# Balancing_Robot_1_2_FTDI.net
KiCad netlist of a schematic drawn in Altium Designer
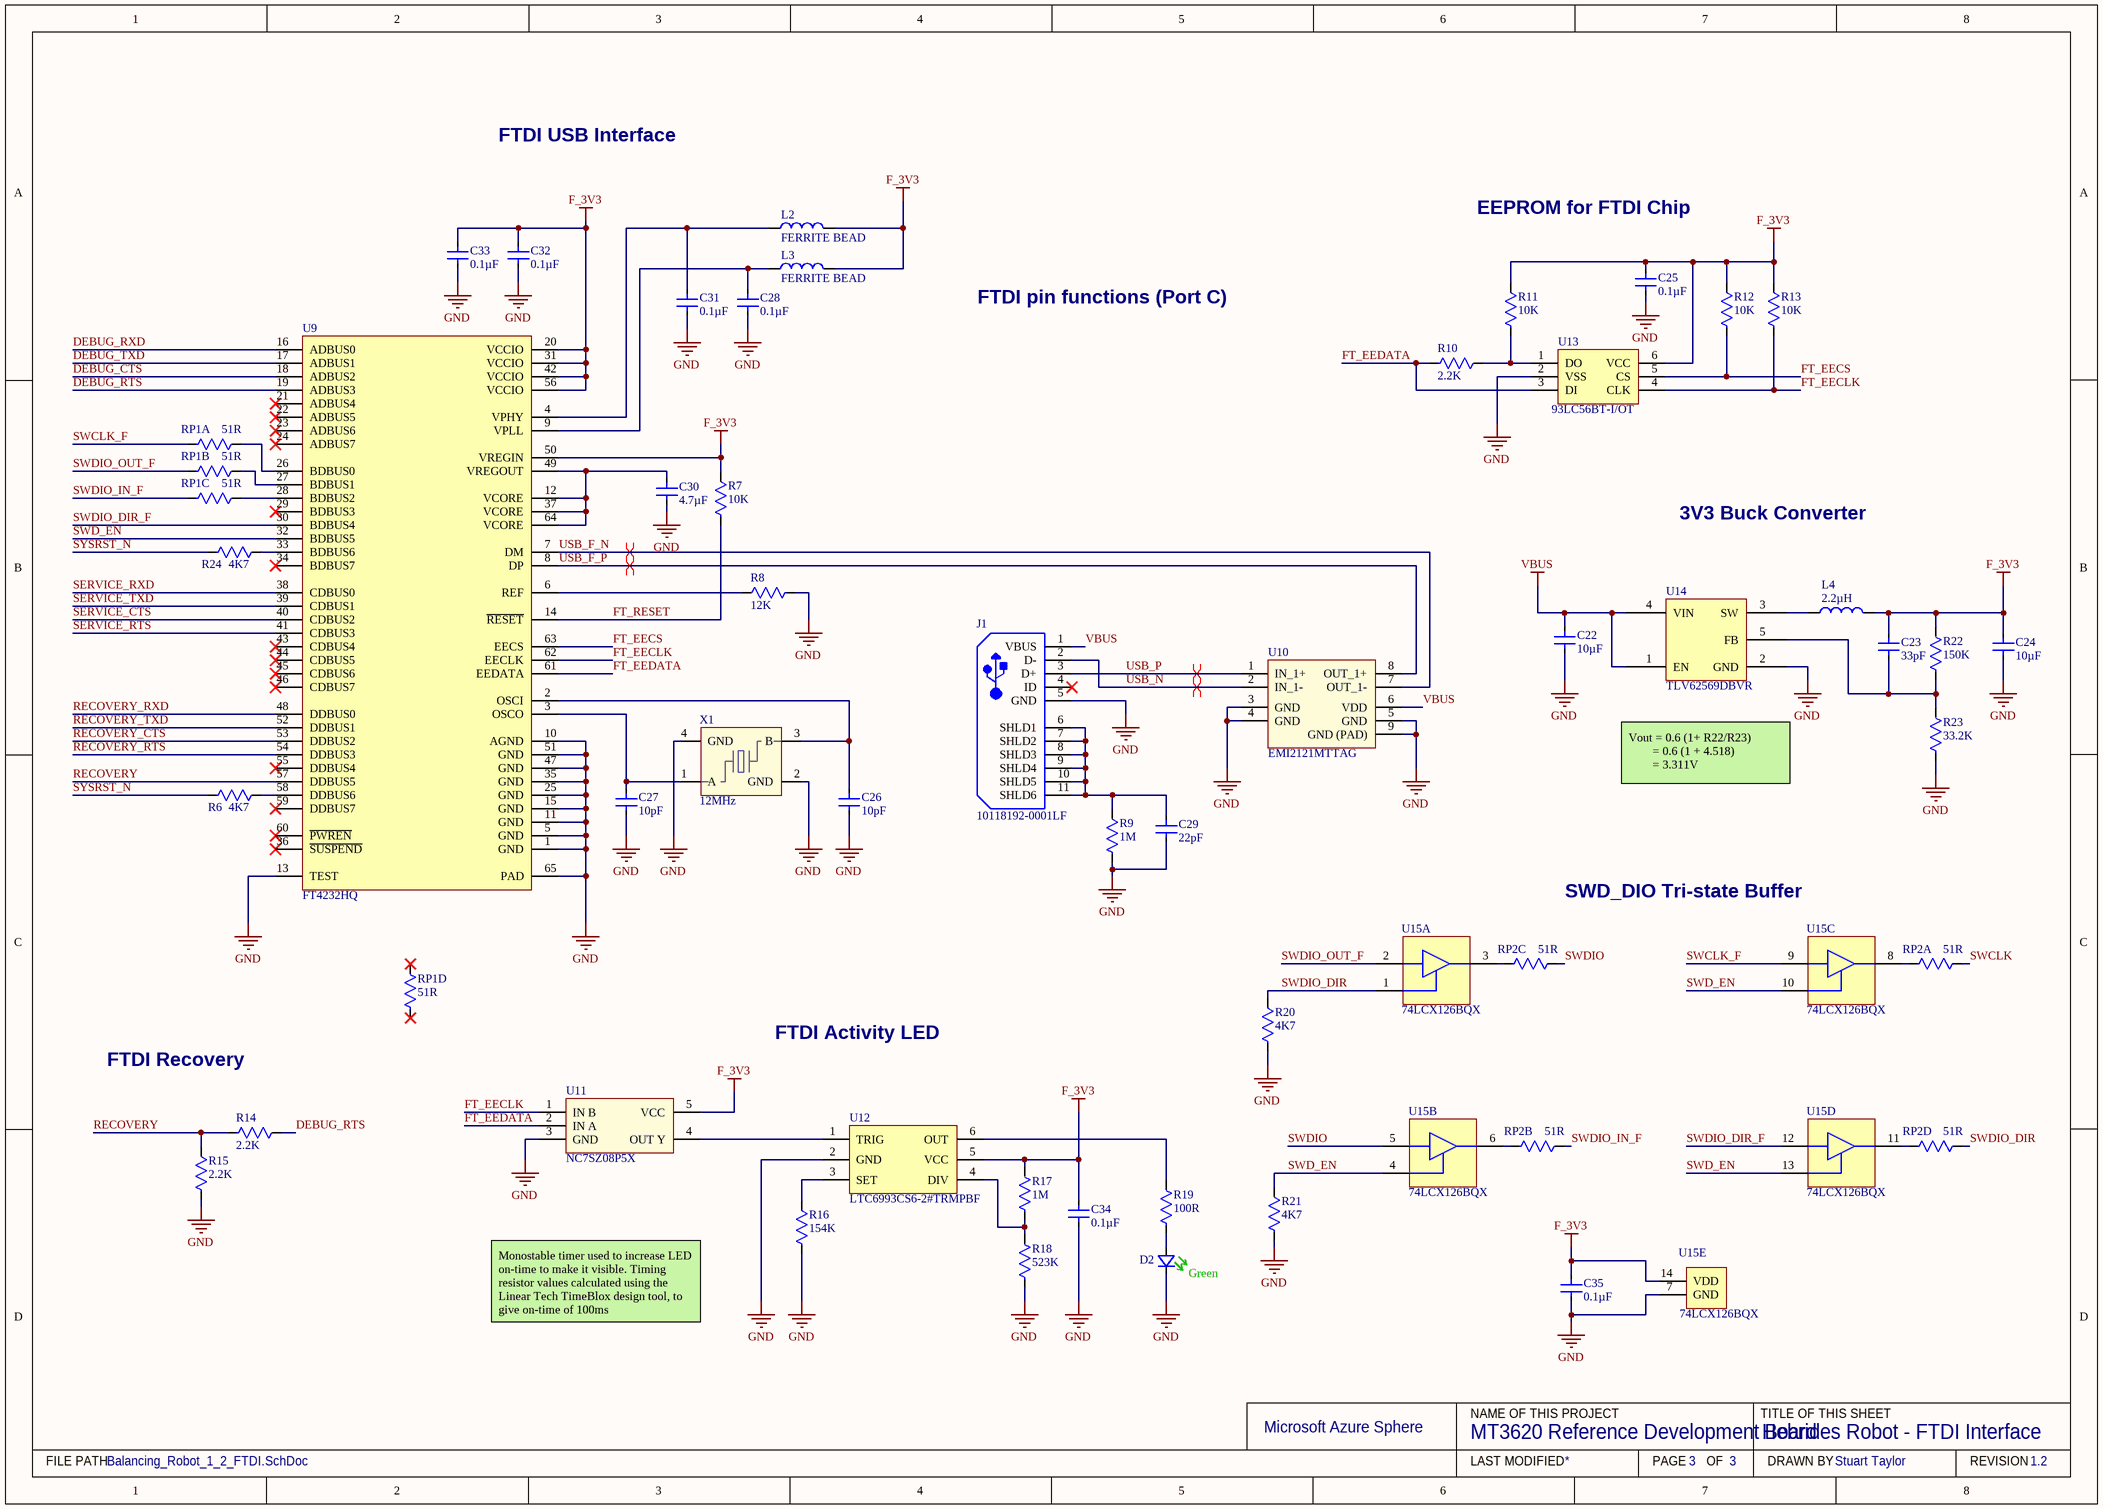
[diagram p0: Balancing_Robot_1_2_FTDI.SchDoc]

(export (version "E")
  (design (tool "Eeschema 10.0.6"))
  (components
    (comp (ref "C22")
      (value "10µF")
      (footprint "CAPC1608-EIA0603-1MM-MED")
      (description "CAP CER 10UF 25V 20% X5R 0603")
      (fields
        (field (name "MANUFACTURER") "TDK Corporation")
        (field (name "MANUFACTURER PART NUMBER") "C1608X5R1E106M080AC")
        (field (name "CAPACITANCE") "10µF")
      )
      (libsource (lib "TDK-Capacitor_C_0603") (part "10µF 0603 X5R 25V"))
    )
    (comp (ref "C23")
      (value "33pF")
      (footprint "CAPC1005-EIA0402 0.55MM MED")
      (description "CAP CER 33PF 50V 5% NP0 0402")
      (fields
        (field (name "MANUFACTURER") "TDK Corporation")
        (field (name "MANUFACTURER PART NUMBER") "C1005C0G1H330J050BA")
        (field (name "CAPACITANCE") "33pF")
      )
      (libsource (lib "TDK_Capacitor_C_0402") (part "33pF 0402 C0G, NP0 50V"))
    )
    (comp (ref "C24")
      (value "10µF")
      (footprint "CAPC1005-EIA0402 0.55MM MED")
      (description "CAP CER 10UF 6.3V 20% X5R 0402")
      (fields
        (field (name "MANUFACTURER") "TDK Corporation")
        (field (name "MANUFACTURER PART NUMBER") "C1005X5R0J106M050BC")
        (field (name "CAPACITANCE") "10µF")
      )
      (libsource (lib "TDK_Capacitor_C_0402") (part "10µF 0402 X5R 6.3V"))
    )
    (comp (ref "C25")
      (value "0.1µF")
      (footprint "CAPC1005-EIA0402 0.55MM MED")
      (description "CAP CER 0.1UF 50V 10% X7R 0402")
      (fields
        (field (name "MANUFACTURER") "TDK Corporation")
        (field (name "MANUFACTURER PART NUMBER") "C1005X7R1H104K050BB")
        (field (name "CAPACITANCE") "0.1µF")
      )
      (libsource (lib "TDK_Capacitor_C_0402") (part "0.1µF 0402 X7R 50V"))
    )
    (comp (ref "C26")
      (value "10pF")
      (footprint "CAPC1005-EIA0402 0.55MM MED")
      (description "CAP CER 10PF 50V NP0 0402")
      (fields
        (field (name "MANUFACTURER") "TDK Corporation")
        (field (name "MANUFACTURER PART NUMBER") "C1005C0G1H100D050BA")
        (field (name "CAPACITANCE") "10pF")
      )
      (libsource (lib "TDK_Capacitor_C_0402") (part "10pF 0402 C0G, NP0 50V"))
    )
    (comp (ref "C27")
      (value "10pF")
      (footprint "CAPC1005-EIA0402 0.55MM MED")
      (description "CAP CER 10PF 50V NP0 0402")
      (fields
        (field (name "MANUFACTURER") "TDK Corporation")
        (field (name "MANUFACTURER PART NUMBER") "C1005C0G1H100D050BA")
        (field (name "CAPACITANCE") "10pF")
      )
      (libsource (lib "TDK_Capacitor_C_0402") (part "10pF 0402 C0G, NP0 50V"))
    )
    (comp (ref "C28")
      (value "0.1µF")
      (footprint "CAPC1005-EIA0402 0.55MM MED")
      (description "CAP CER 0.1UF 50V 10% X7R 0402")
      (fields
        (field (name "MANUFACTURER") "TDK Corporation")
        (field (name "MANUFACTURER PART NUMBER") "C1005X7R1H104K050BB")
        (field (name "CAPACITANCE") "0.1µF")
      )
      (libsource (lib "TDK_Capacitor_C_0402") (part "0.1µF 0402 X7R 50V"))
    )
    (comp (ref "C29")
      (value "22pF")
      (footprint "CAPC1005-EIA0402 0.55MM MED")
      (description "CAP CER 22PF 50V 5% NP0 0402")
      (fields
        (field (name "MANUFACTURER") "TDK Corporation")
        (field (name "MANUFACTURER PART NUMBER") "C1005C0G1H220J050BA")
        (field (name "CAPACITANCE") "22pF")
      )
      (libsource (lib "TDK_Capacitor_C_0402") (part "22pF 0402 C0G, NP0 50V"))
    )
    (comp (ref "C30")
      (value "4.7µF")
      (footprint "CAPC1005-EIA0402 0.55MM MED")
      (description "CAP CER 4.7UF 10V 10% X5R 0402")
      (fields
        (field (name "MANUFACTURER") "TDK Corporation")
        (field (name "MANUFACTURER PART NUMBER") "C1005X5R1A475K050BC")
        (field (name "CAPACITANCE") "4.7µF")
      )
      (libsource (lib "TDK_Capacitor_C_0402") (part "4.7µF 0402 X5R 10V"))
    )
    (comp (ref "C31")
      (value "0.1µF")
      (footprint "CAPC1005-EIA0402 0.55MM MED")
      (description "CAP CER 0.1UF 50V 10% X7R 0402")
      (fields
        (field (name "MANUFACTURER") "TDK Corporation")
        (field (name "MANUFACTURER PART NUMBER") "C1005X7R1H104K050BB")
        (field (name "CAPACITANCE") "0.1µF")
      )
      (libsource (lib "TDK_Capacitor_C_0402") (part "0.1µF 0402 X7R 50V"))
    )
    (comp (ref "C32")
      (value "0.1µF")
      (footprint "CAPC1005-EIA0402 0.55MM MED")
      (description "CAP CER 0.1UF 50V 10% X7R 0402")
      (fields
        (field (name "MANUFACTURER") "TDK Corporation")
        (field (name "MANUFACTURER PART NUMBER") "C1005X7R1H104K050BB")
        (field (name "CAPACITANCE") "0.1µF")
      )
      (libsource (lib "TDK_Capacitor_C_0402") (part "0.1µF 0402 X7R 50V"))
    )
    (comp (ref "C33")
      (value "0.1µF")
      (footprint "CAPC1005-EIA0402 0.55MM MED")
      (description "CAP CER 0.1UF 50V 10% X7R 0402")
      (fields
        (field (name "MANUFACTURER") "TDK Corporation")
        (field (name "MANUFACTURER PART NUMBER") "C1005X7R1H104K050BB")
        (field (name "CAPACITANCE") "0.1µF")
      )
      (libsource (lib "TDK_Capacitor_C_0402") (part "0.1µF 0402 X7R 50V"))
    )
    (comp (ref "C34")
      (value "0.1µF")
      (footprint "CAPC1005-EIA0402 0.55MM MED")
      (description "CAP CER 0.1UF 50V 10% X7R 0402")
      (fields
        (field (name "MANUFACTURER") "TDK Corporation")
        (field (name "MANUFACTURER PART NUMBER") "C1005X7R1H104K050BB")
        (field (name "CAPACITANCE") "0.1µF")
      )
      (libsource (lib "TDK_Capacitor_C_0402") (part "0.1µF 0402 X7R 50V"))
    )
    (comp (ref "C35")
      (value "0.1µF")
      (footprint "CAPC1005-EIA0402 0.55MM MED")
      (description "CAP CER 0.1UF 50V 10% X7R 0402")
      (fields
        (field (name "MANUFACTURER") "TDK Corporation")
        (field (name "MANUFACTURER PART NUMBER") "C1005X7R1H104K050BB")
        (field (name "CAPACITANCE") "0.1µF")
      )
      (libsource (lib "TDK_Capacitor_C_0402") (part "0.1µF 0402 X7R 50V"))
    )
    (comp (ref "D2")
      (value "Green LED")
      (footprint "Rohm SML-D12 Green")
      (description "1.6 x 0.8 x 0.55mm (0603) LED 560nm Green")
      (fields
        (field (name "MANUFACTURER") "Rohm Semiconductor")
        (field (name "MANUFACTURER PART NUMBER") "SML-D12P8WT86")
        (field (name "COLOUR") "Green")
      )
      (libsource (lib "Rohm") (part "SML-D12P"))
    )
    (comp (ref "J1")
      (value "Amphenol FCI 10118192-0001LF")
      (footprint "FCI-10118192-0001LF-5_V")
      (description "USB micro B with no TH anchors")
      (fields
        (field (name "MANUFACTURER") "Amphenol FCI")
        (field (name "MANUFACTURER PART NUMBER") "10118192-0001LF")
        (field (name "CREATED BY") "HUGHWI")
      )
      (libsource (lib "Amphenol") (part "Amphenol FCI 10118192-0001LF"))
    )
    (comp (ref "L2")
      (value "FERRITE BEAD")
      (footprint "CAPC1005-EIA0402 0.55MM MED")
      (description "FERRITE BEAD 120 OHM 0402 1LN")
      (fields
        (field (name "MANUFACTURER") "Murata Electronics North America")
        (field (name "MANUFACTURER PART NUMBER") "BLM15PD121SN1D")
      )
      (libsource (lib "Murata") (part "BLM15PD121SN1D"))
    )
    (comp (ref "L3")
      (value "FERRITE BEAD")
      (footprint "CAPC1005-EIA0402 0.55MM MED")
      (description "FERRITE BEAD 120 OHM 0402 1LN")
      (fields
        (field (name "MANUFACTURER") "Murata Electronics North America")
        (field (name "MANUFACTURER PART NUMBER") "BLM15PD121SN1D")
      )
      (libsource (lib "Murata") (part "BLM15PD121SN1D"))
    )
    (comp (ref "L4")
      (value "2.2µH")
      (footprint "NR3015T2R2M")
      (description "FIXED IND 2.2UH 1.5A 72 MOHM SMD")
      (fields
        (field (name "MANUFACTURER") "Taiyo Yuden")
        (field (name "MANUFACTURER PART NUMBER") "NR3015T2R2M")
      )
      (libsource (lib "TaiyoYuden ") (part "NR3015T2R2M"))
    )
    (comp (ref "R6")
      (value "4K7")
      (footprint "RES 0402 MEDIUM DENSITY")
      (description "RES 4.7K OHM 1/10W 1% 0402 SMD")
      (fields
        (field (name "MANUFACTURER") "Panasonic Electronic Components")
        (field (name "MANUFACTURER PART NUMBER") "ERJ-2RKF4701X")
        (field (name "RESISTANCE (OHMS)") "4K7")
      )
      (libsource (lib "Panasonic_Resistor_ERJ2R") (part "4.7K"))
    )
    (comp (ref "R7")
      (value "10K")
      (footprint "RES 0402 MEDIUM DENSITY")
      (description "RES 10K OHM 1/10W 1% 0402 SMD")
      (fields
        (field (name "MANUFACTURER") "Panasonic Electronic Components")
        (field (name "MANUFACTURER PART NUMBER") "ERJ-2RKF1002X")
        (field (name "RESISTANCE (OHMS)") "10K")
      )
      (libsource (lib "Panasonic_Resistor_ERJ2R") (part "10K"))
    )
    (comp (ref "R8")
      (value "12K")
      (footprint "RES 0402 MEDIUM DENSITY")
      (description "RES 12K OHM 1/10W 1% 0402 SMD")
      (fields
        (field (name "MANUFACTURER") "Panasonic Electronic Components")
        (field (name "MANUFACTURER PART NUMBER") "ERJ-2RKF1202X")
        (field (name "RESISTANCE (OHMS)") "12K")
      )
      (libsource (lib "Panasonic_Resistor_ERJ2R") (part "12K"))
    )
    (comp (ref "R9")
      (value "1M")
      (footprint "RES 0402 MEDIUM DENSITY")
      (description "RES 1M OHM 1/10W 1% 0402 SMD")
      (fields
        (field (name "MANUFACTURER") "Panasonic Electronic Components")
        (field (name "MANUFACTURER PART NUMBER") "ERJ-2RKF1004X")
        (field (name "RESISTANCE (OHMS)") "1M")
      )
      (libsource (lib "Panasonic_Resistor_ERJ2R") (part "1M"))
    )
    (comp (ref "R10")
      (value "2.2K")
      (footprint "RES 0402 MEDIUM DENSITY")
      (description "RES 2.2K OHM 1/10W 1% 0402 SMD")
      (fields
        (field (name "MANUFACTURER") "Panasonic Electronic Components")
        (field (name "MANUFACTURER PART NUMBER") "ERJ-2RKF2201X")
        (field (name "RESISTANCE (OHMS)") "2.2K")
      )
      (libsource (lib "Panasonic_Resistor_ERJ2R") (part "2.2K"))
    )
    (comp (ref "R11")
      (value "10K")
      (footprint "RES 0402 MEDIUM DENSITY")
      (description "RES 10K OHM 1/10W 1% 0402 SMD")
      (fields
        (field (name "MANUFACTURER") "Panasonic Electronic Components")
        (field (name "MANUFACTURER PART NUMBER") "ERJ-2RKF1002X")
        (field (name "RESISTANCE (OHMS)") "10K")
      )
      (libsource (lib "Panasonic_Resistor_ERJ2R") (part "10K"))
    )
    (comp (ref "R12")
      (value "10K")
      (footprint "RES 0402 MEDIUM DENSITY")
      (description "RES 10K OHM 1/10W 1% 0402 SMD")
      (fields
        (field (name "MANUFACTURER") "Panasonic Electronic Components")
        (field (name "MANUFACTURER PART NUMBER") "ERJ-2RKF1002X")
        (field (name "RESISTANCE (OHMS)") "10K")
      )
      (libsource (lib "Panasonic_Resistor_ERJ2R") (part "10K"))
    )
    (comp (ref "R13")
      (value "10K")
      (footprint "RES 0402 MEDIUM DENSITY")
      (description "RES 10K OHM 1/10W 1% 0402 SMD")
      (fields
        (field (name "MANUFACTURER") "Panasonic Electronic Components")
        (field (name "MANUFACTURER PART NUMBER") "ERJ-2RKF1002X")
        (field (name "RESISTANCE (OHMS)") "10K")
      )
      (libsource (lib "Panasonic_Resistor_ERJ2R") (part "10K"))
    )
    (comp (ref "R14")
      (value "2.2K")
      (footprint "RES 0402 MEDIUM DENSITY")
      (description "RES 2.2K OHM 1/10W 1% 0402 SMD")
      (fields
        (field (name "MANUFACTURER") "Panasonic Electronic Components")
        (field (name "MANUFACTURER PART NUMBER") "ERJ-2RKF2201X")
        (field (name "RESISTANCE (OHMS)") "2.2K")
      )
      (libsource (lib "Panasonic_Resistor_ERJ2R") (part "2.2K"))
    )
    (comp (ref "R15")
      (value "2.2K")
      (footprint "RES 0402 MEDIUM DENSITY")
      (description "RES 2.2K OHM 1/10W 1% 0402 SMD")
      (fields
        (field (name "MANUFACTURER") "Panasonic Electronic Components")
        (field (name "MANUFACTURER PART NUMBER") "ERJ-2RKF2201X")
        (field (name "RESISTANCE (OHMS)") "2.2K")
      )
      (libsource (lib "Panasonic_Resistor_ERJ2R") (part "2.2K"))
    )
    (comp (ref "R16")
      (value "154K")
      (footprint "RES 0402 MEDIUM DENSITY")
      (description "RES 154K OHM 1/10W 1% 0402 SMD")
      (fields
        (field (name "MANUFACTURER") "Panasonic Electronic Components")
        (field (name "MANUFACTURER PART NUMBER") "ERJ-2RKF1543X")
        (field (name "RESISTANCE (OHMS)") "154K")
      )
      (libsource (lib "Panasonic_Resistor_ERJ2R") (part "154K"))
    )
    (comp (ref "R17")
      (value "1M")
      (footprint "RES 0402 MEDIUM DENSITY")
      (description "RES 1M OHM 1/10W 1% 0402 SMD")
      (fields
        (field (name "MANUFACTURER") "Panasonic Electronic Components")
        (field (name "MANUFACTURER PART NUMBER") "ERJ-2RKF1004X")
        (field (name "RESISTANCE (OHMS)") "1M")
      )
      (libsource (lib "Panasonic_Resistor_ERJ2R") (part "1M"))
    )
    (comp (ref "R18")
      (value "523K")
      (footprint "RES 0402 MEDIUM DENSITY")
      (description "RES 523K OHM 1/10W 1% 0402 SMD")
      (fields
        (field (name "MANUFACTURER") "Panasonic Electronic Components")
        (field (name "MANUFACTURER PART NUMBER") "ERJ-2RKF5233X")
        (field (name "RESISTANCE (OHMS)") "523K")
      )
      (libsource (lib "Panasonic_Resistor_ERJ2R") (part "523K"))
    )
    (comp (ref "R19")
      (value "100R")
      (footprint "RES 0402 MEDIUM DENSITY")
      (description "RES 100 OHM 1/10W 1% 0402 SMD")
      (fields
        (field (name "MANUFACTURER") "Panasonic Electronic Components")
        (field (name "MANUFACTURER PART NUMBER") "ERJ-2RKF1000X")
        (field (name "RESISTANCE (OHMS)") "100R")
      )
      (libsource (lib "Panasonic_Resistor_ERJ2R") (part "100R"))
    )
    (comp (ref "R20")
      (value "4K7")
      (footprint "RES 0402 MEDIUM DENSITY")
      (description "RES 4.7K OHM 1/10W 1% 0402 SMD")
      (fields
        (field (name "MANUFACTURER") "Panasonic Electronic Components")
        (field (name "MANUFACTURER PART NUMBER") "ERJ-2RKF4701X")
        (field (name "RESISTANCE (OHMS)") "4K7")
      )
      (libsource (lib "Panasonic_Resistor_ERJ2R") (part "4.7K"))
    )
    (comp (ref "R21")
      (value "4K7")
      (footprint "RES 0402 MEDIUM DENSITY")
      (description "RES 4.7K OHM 1/10W 1% 0402 SMD")
      (fields
        (field (name "MANUFACTURER") "Panasonic Electronic Components")
        (field (name "MANUFACTURER PART NUMBER") "ERJ-2RKF4701X")
        (field (name "RESISTANCE (OHMS)") "4K7")
      )
      (libsource (lib "Panasonic_Resistor_ERJ2R") (part "4.7K"))
    )
    (comp (ref "R22")
      (value "150K")
      (footprint "RES 0402 MEDIUM DENSITY")
      (description "RES 150K OHM 1/10W 1% 0402 SMD")
      (fields
        (field (name "MANUFACTURER") "Panasonic Electronic Components")
        (field (name "MANUFACTURER PART NUMBER") "ERJ-2RKF1503X")
        (field (name "RESISTANCE (OHMS)") "150K")
      )
      (libsource (lib "Panasonic_Resistor_ERJ2R") (part "150K"))
    )
    (comp (ref "R23")
      (value "33.2K")
      (footprint "RES 0402 MEDIUM DENSITY")
      (description "RES 33.2K OHM 1/10W 1% 0402 SMD")
      (fields
        (field (name "MANUFACTURER") "Panasonic Electronic Components")
        (field (name "MANUFACTURER PART NUMBER") "ERJ-2RKF3322X")
        (field (name "RESISTANCE (OHMS)") "33.2K")
      )
      (libsource (lib "Panasonic_Resistor_ERJ2R") (part "33.2K"))
    )
    (comp (ref "R24")
      (value "4K7")
      (footprint "RES 0402 MEDIUM DENSITY")
      (description "RES 4.7K OHM 1/10W 1% 0402 SMD")
      (fields
        (field (name "MANUFACTURER") "Panasonic Electronic Components")
        (field (name "MANUFACTURER PART NUMBER") "ERJ-2RKF4701X")
        (field (name "RESISTANCE (OHMS)") "4K7")
      )
      (libsource (lib "Panasonic_Resistor_ERJ2R") (part "4.7K"))
    )
    (comp (ref "RP1")
      (value "51R")
      (footprint "EXB-N8V")
      (fields
        (field (name "MANUFACTURER") "Panasonic / Panasonic ECG")
        (field (name "MANUFACTURER PART NUMBER") "EXB-N8V510JX")
      )
      (libsource (lib "Panasonic") (part "EXB-N8V510JX"))
    )
    (comp (ref "RP2")
      (value "51R")
      (footprint "EXB-N8V")
      (fields
        (field (name "MANUFACTURER") "Panasonic / Panasonic ECG")
        (field (name "MANUFACTURER PART NUMBER") "EXB-N8V510JX")
      )
      (libsource (lib "Panasonic") (part "EXB-N8V510JX"))
    )
    (comp (ref "U9")
      (value "FT4232HQ")
      (footprint "FTDI_TF4232HQ_64QFN")
      (description "IC USB HS QUAD UART/SYNC 64-QFN")
      (fields
        (field (name "MANUFACTURER") "FTDI, Future Technology Devices International Ltd")
        (field (name "MANUFACTURER PART NUMBER") "FT4232HQ-REEL")
      )
      (libsource (lib "FTDI") (part "FT4232HQ"))
    )
    (comp (ref "U10")
      (value "EMI2121MTTAG")
      (footprint "EMI2121MTTAG")
      (description "IC FILTER COMMON MODE ESD 8WDFN")
      (fields (field (name "MANUFACTURER") "ON Semiconductor"))
      (libsource (lib "OnSemiconductor") (part "EMI2121MTTAG"))
    )
    (comp (ref "U11")
      (value "NC7SZ08P5X")
      (footprint "SC-70-5")
      (description "IC GATE AND 1CH 2-INP SC-70-5")
      (fields (field (name "MANUFACTURER") "Fairchild Semiconductor"))
      (libsource (lib "OnSemiconductor") (part "NC7SZ08P5X"))
    )
    (comp (ref "U12")
      (value "LTC6993CS6-2#TRMPBF")
      (footprint "LTC6993CS6-2#TRMPBF")
      (description "LINEAR TECHNOLOGY - LTC6993CS6-2#TRMPBF - GENERATOR, PULSE, TIMERBLOX, 6SOT-23")
      (fields (field (name "MANUFACTURER") "LINEAR TECHNOLOGY"))
      (libsource (lib "LinearTech") (part "LTC6993CS6-2#TRMPBF"))
    )
    (comp (ref "U13")
      (value "93LC56BT-I/OT")
      (footprint "SOT23-93C56B")
      (description "IC EEPROM 2KBIT 2MHZ SOT23-6")
      (fields (field (name "MANUFACTURER") "Microchip Technology"))
      (libsource (lib "Microchip") (part "93LC56BT-I/OT"))
    )
    (comp (ref "U14")
      (value "TLV62569DBVR")
      (footprint "TI-SOT23-6")
      (description "Variable voltage buck converter")
      (fields (field (name "MANUFACTURER") "Texas Instruments"))
      (libsource (lib "TexasInstruments") (part "TLV62569DBVR"))
    )
    (comp (ref "U15")
      (value "74LCX126BQX")
      (footprint "74LCX126BQX")
      (description "IC BUFFER QUAD LV N-INV 14DQFN")
      (fields (field (name "MANUFACTURER") "Fairchild Semiconductor"))
      (libsource (lib "OnSemiconductor") (part "74LCX126BQX"))
    )
    (comp (ref "X1")
      (value "12MHz")
      (footprint "TXC 8Z")
      (description "CRYSTAL 12.000 MHZ 18PF SMD")
      (fields
        (field (name "MANUFACTURER") "TXC CORPORATION")
        (field (name "MANUFACTURER PART NUMBER") "8Z-12.000MAAJ-T")
        (field (name "FREQUENCY") "12MHz")
      )
      (libsource (lib "crystal") (part "CRYSTAL 12MHz 18pF SMD"))
    )
  )
  (nets
    (net (code "1") (name "/DEBUG_CTS") (class "Default")
      (node (ref "U9") (pin "18") (pinfunction "ADBUS2_18") (pintype "passive"))
    )
    (net (code "2") (name "/DEBUG_RTS") (class "Default")
      (node (ref "R14") (pin "1") (pinfunction "1_1") (pintype "passive"))
      (node (ref "U9") (pin "19") (pinfunction "ADBUS3_19") (pintype "passive"))
    )
    (net (code "3") (name "/DEBUG_RXD") (class "Default")
      (node (ref "U9") (pin "16") (pinfunction "ADBUS0_16") (pintype "passive"))
    )
    (net (code "4") (name "/DEBUG_TXD") (class "Default")
      (node (ref "U9") (pin "17") (pinfunction "ADBUS1_17") (pintype "passive"))
    )
    (net (code "5") (name "/FT_EECLK") (class "Default")
      (node (ref "R13") (pin "2") (pinfunction "2_2") (pintype "passive"))
      (node (ref "U11") (pin "1") (pinfunction "IN_B_1") (pintype "passive"))
      (node (ref "U13") (pin "4") (pinfunction "CLK_4") (pintype "passive"))
      (node (ref "U9") (pin "62") (pinfunction "EECLK_62") (pintype "passive"))
    )
    (net (code "6") (name "/FT_EECS") (class "Default")
      (node (ref "R12") (pin "2") (pinfunction "2_2") (pintype "passive"))
      (node (ref "U13") (pin "5") (pinfunction "CS_5") (pintype "passive"))
      (node (ref "U9") (pin "63") (pinfunction "EECS_63") (pintype "passive"))
    )
    (net (code "7") (name "/FT_EEDATA") (class "Default")
      (node (ref "R10") (pin "2") (pinfunction "2_2") (pintype "passive"))
      (node (ref "U11") (pin "2") (pinfunction "IN_A_2") (pintype "passive"))
      (node (ref "U13") (pin "3") (pinfunction "DI_3") (pintype "passive"))
      (node (ref "U9") (pin "61") (pinfunction "EEDATA_61") (pintype "passive"))
    )
    (net (code "8") (name "/FT_RESET") (class "Default")
      (node (ref "R7") (pin "2") (pinfunction "2_2") (pintype "passive"))
      (node (ref "U9") (pin "14") (pinfunction "~{RESET}_14") (pintype "passive"))
    )
    (net (code "9") (name "/RECOVERY") (class "Default")
      (node (ref "R14") (pin "2") (pinfunction "2_2") (pintype "passive"))
      (node (ref "R15") (pin "1") (pinfunction "1_1") (pintype "passive"))
      (node (ref "U9") (pin "57") (pinfunction "DDBUS5_57") (pintype "passive"))
    )
    (net (code "10") (name "/RECOVERY_CTS") (class "Default")
      (node (ref "U9") (pin "53") (pinfunction "DDBUS2_53") (pintype "passive"))
    )
    (net (code "11") (name "/RECOVERY_RTS") (class "Default")
      (node (ref "U9") (pin "54") (pinfunction "DDBUS3_54") (pintype "passive"))
    )
    (net (code "12") (name "/RECOVERY_RXD") (class "Default")
      (node (ref "U9") (pin "48") (pinfunction "DDBUS0_48") (pintype "passive"))
    )
    (net (code "13") (name "/RECOVERY_TXD") (class "Default")
      (node (ref "U9") (pin "52") (pinfunction "DDBUS1_52") (pintype "passive"))
    )
    (net (code "14") (name "/SERVICE_CTS") (class "Default")
      (node (ref "U9") (pin "40") (pinfunction "CDBUS2_40") (pintype "passive"))
    )
    (net (code "15") (name "/SERVICE_RTS") (class "Default")
      (node (ref "U9") (pin "41") (pinfunction "CDBUS3_41") (pintype "passive"))
    )
    (net (code "16") (name "/SERVICE_RXD") (class "Default")
      (node (ref "U9") (pin "38") (pinfunction "CDBUS0_38") (pintype "passive"))
    )
    (net (code "17") (name "/SERVICE_TXD") (class "Default")
      (node (ref "U9") (pin "39") (pinfunction "CDBUS1_39") (pintype "passive"))
    )
    (net (code "18") (name "/SWCLK") (class "Default")
      (node (ref "RP2") (pin "2") (pinfunction "2_2") (pintype "passive"))
    )
    (net (code "19") (name "/SWCLK_F") (class "Default")
      (node (ref "RP1") (pin "1") (pinfunction "1_1") (pintype "passive"))
      (node (ref "U15") (pin "9") (pinfunction "3A_9") (pintype "passive"))
    )
    (net (code "20") (name "/SWDIO") (class "Default")
      (node (ref "RP2") (pin "6") (pinfunction "6_6") (pintype "passive"))
      (node (ref "U15") (pin "5") (pinfunction "2A_5") (pintype "passive"))
    )
    (net (code "21") (name "/SWDIO_DIR") (class "Default")
      (node (ref "R20") (pin "1") (pinfunction "1_1") (pintype "passive"))
      (node (ref "RP2") (pin "8") (pinfunction "8_8") (pintype "passive"))
      (node (ref "U15") (pin "1") (pinfunction "1OE_1") (pintype "passive"))
    )
    (net (code "22") (name "/SWDIO_DIR_F") (class "Default")
      (node (ref "U15") (pin "12") (pinfunction "4A_12") (pintype "passive"))
      (node (ref "U9") (pin "30") (pinfunction "BDBUS4_30") (pintype "passive"))
    )
    (net (code "23") (name "/SWDIO_IN_F") (class "Default")
      (node (ref "RP1") (pin "5") (pinfunction "5_5") (pintype "passive"))
      (node (ref "RP2") (pin "4") (pinfunction "4_4") (pintype "passive"))
    )
    (net (code "24") (name "/SWDIO_OUT_F") (class "Default")
      (node (ref "RP1") (pin "3") (pinfunction "3_3") (pintype "passive"))
      (node (ref "U15") (pin "2") (pinfunction "1A_2") (pintype "passive"))
    )
    (net (code "25") (name "/SWD_EN") (class "Default")
      (node (ref "R21") (pin "1") (pinfunction "1_1") (pintype "passive"))
      (node (ref "U15") (pin "10") (pinfunction "3OE_10") (pintype "passive"))
      (node (ref "U15") (pin "13") (pinfunction "4OE_13") (pintype "passive"))
      (node (ref "U15") (pin "4") (pinfunction "2OE_4") (pintype "passive"))
      (node (ref "U9") (pin "32") (pinfunction "BDBUS5_32") (pintype "passive"))
    )
    (net (code "26") (name "/SYSRST_N") (class "Default")
      (node (ref "R24") (pin "2") (pinfunction "2_2") (pintype "passive"))
      (node (ref "R6") (pin "2") (pinfunction "2_2") (pintype "passive"))
    )
    (net (code "27") (name "/USB_F_N") (class "Default")
      (node (ref "U10") (pin "7") (pinfunction "OUT_1-_7") (pintype "passive"))
      (node (ref "U9") (pin "7") (pinfunction "DM_7") (pintype "passive"))
    )
    (net (code "28") (name "/USB_F_P") (class "Default")
      (node (ref "U10") (pin "8") (pinfunction "OUT_1+_8") (pintype "passive"))
      (node (ref "U9") (pin "8") (pinfunction "DP_8") (pintype "passive"))
    )
    (net (code "29") (name "/USB_N") (class "Default")
      (node (ref "J1") (pin "2") (pinfunction "D-_2") (pintype "passive"))
      (node (ref "U10") (pin "2") (pinfunction "IN_1-_2") (pintype "passive"))
    )
    (net (code "30") (name "/USB_P") (class "Default")
      (node (ref "J1") (pin "3") (pinfunction "D+_3") (pintype "passive"))
      (node (ref "U10") (pin "1") (pinfunction "IN_1+_1") (pintype "passive"))
    )
    (net (code "31") (name "F_3V3") (class "Default")
      (node (ref "C23") (pin "2") (pinfunction "2_2") (pintype "passive"))
      (node (ref "C24") (pin "2") (pinfunction "2_2") (pintype "passive"))
      (node (ref "C25") (pin "2") (pinfunction "2_2") (pintype "passive"))
      (node (ref "C32") (pin "2") (pinfunction "2_2") (pintype "passive"))
      (node (ref "C33") (pin "2") (pinfunction "2_2") (pintype "passive"))
      (node (ref "C34") (pin "2") (pinfunction "2_2") (pintype "passive"))
      (node (ref "C35") (pin "2") (pinfunction "2_2") (pintype "passive"))
      (node (ref "L2") (pin "2") (pinfunction "2_2") (pintype "passive"))
      (node (ref "L3") (pin "2") (pinfunction "2_2") (pintype "passive"))
      (node (ref "L4") (pin "2") (pinfunction "2_2") (pintype "passive"))
      (node (ref "R11") (pin "1") (pinfunction "1_1") (pintype "passive"))
      (node (ref "R12") (pin "1") (pinfunction "1_1") (pintype "passive"))
      (node (ref "R13") (pin "1") (pinfunction "1_1") (pintype "passive"))
      (node (ref "R17") (pin "1") (pinfunction "1_1") (pintype "passive"))
      (node (ref "R22") (pin "1") (pinfunction "1_1") (pintype "passive"))
      (node (ref "R7") (pin "1") (pinfunction "1_1") (pintype "passive"))
      (node (ref "U11") (pin "5") (pinfunction "VCC_5") (pintype "passive"))
      (node (ref "U12") (pin "5") (pinfunction "VCC_5") (pintype "passive"))
      (node (ref "U13") (pin "6") (pinfunction "VCC_6") (pintype "passive"))
      (node (ref "U15") (pin "14") (pinfunction "VDD_14") (pintype "passive"))
      (node (ref "U9") (pin "20") (pinfunction "VCCIO_20") (pintype "passive"))
      (node (ref "U9") (pin "31") (pinfunction "VCCIO_31") (pintype "passive"))
      (node (ref "U9") (pin "42") (pinfunction "VCCIO_42") (pintype "passive"))
      (node (ref "U9") (pin "50") (pinfunction "VREGIN_50") (pintype "passive"))
      (node (ref "U9") (pin "56") (pinfunction "VCCIO_56") (pintype "passive"))
    )
    (net (code "32") (name "GND") (class "Default")
      (node (ref "C22") (pin "1") (pinfunction "1_1") (pintype "passive"))
      (node (ref "C24") (pin "1") (pinfunction "1_1") (pintype "passive"))
      (node (ref "C25") (pin "1") (pinfunction "1_1") (pintype "passive"))
      (node (ref "C26") (pin "1") (pinfunction "1_1") (pintype "passive"))
      (node (ref "C27") (pin "1") (pinfunction "1_1") (pintype "passive"))
      (node (ref "C28") (pin "1") (pinfunction "1_1") (pintype "passive"))
      (node (ref "C29") (pin "1") (pinfunction "1_1") (pintype "passive"))
      (node (ref "C30") (pin "1") (pinfunction "1_1") (pintype "passive"))
      (node (ref "C31") (pin "1") (pinfunction "1_1") (pintype "passive"))
      (node (ref "C32") (pin "1") (pinfunction "1_1") (pintype "passive"))
      (node (ref "C33") (pin "1") (pinfunction "1_1") (pintype "passive"))
      (node (ref "C34") (pin "1") (pinfunction "1_1") (pintype "passive"))
      (node (ref "C35") (pin "1") (pinfunction "1_1") (pintype "passive"))
      (node (ref "D2") (pin "1") (pinfunction "K_1") (pintype "passive"))
      (node (ref "J1") (pin "5") (pinfunction "GND_5") (pintype "passive"))
      (node (ref "R15") (pin "2") (pinfunction "2_2") (pintype "passive"))
      (node (ref "R16") (pin "2") (pinfunction "2_2") (pintype "passive"))
      (node (ref "R18") (pin "2") (pinfunction "2_2") (pintype "passive"))
      (node (ref "R20") (pin "2") (pinfunction "2_2") (pintype "passive"))
      (node (ref "R21") (pin "2") (pinfunction "2_2") (pintype "passive"))
      (node (ref "R23") (pin "2") (pinfunction "2_2") (pintype "passive"))
      (node (ref "R8") (pin "2") (pinfunction "2_2") (pintype "passive"))
      (node (ref "R9") (pin "2") (pinfunction "2_2") (pintype "passive"))
      (node (ref "U10") (pin "3") (pinfunction "GND_3") (pintype "passive"))
      (node (ref "U10") (pin "4") (pinfunction "GND_4") (pintype "passive"))
      (node (ref "U10") (pin "5") (pinfunction "GND_5") (pintype "passive"))
      (node (ref "U10") (pin "9") (pinfunction "GND_(PAD)_9") (pintype "passive"))
      (node (ref "U11") (pin "3") (pinfunction "GND_3") (pintype "passive"))
      (node (ref "U12") (pin "2") (pinfunction "GND_2") (pintype "passive"))
      (node (ref "U13") (pin "2") (pinfunction "VSS_2") (pintype "passive"))
      (node (ref "U14") (pin "2") (pinfunction "GND_2") (pintype "passive"))
      (node (ref "U15") (pin "7") (pinfunction "GND_7") (pintype "passive"))
      (node (ref "U9") (pin "1") (pinfunction "GND_1") (pintype "passive"))
      (node (ref "U9") (pin "10") (pinfunction "AGND_10") (pintype "passive"))
      (node (ref "U9") (pin "11") (pinfunction "GND_11") (pintype "passive"))
      (node (ref "U9") (pin "13") (pinfunction "TEST_13") (pintype "passive"))
      (node (ref "U9") (pin "15") (pinfunction "GND_15") (pintype "passive"))
      (node (ref "U9") (pin "25") (pinfunction "GND_25") (pintype "passive"))
      (node (ref "U9") (pin "35") (pinfunction "GND_35") (pintype "passive"))
      (node (ref "U9") (pin "47") (pinfunction "GND_47") (pintype "passive"))
      (node (ref "U9") (pin "5") (pinfunction "GND_5") (pintype "passive"))
      (node (ref "U9") (pin "51") (pinfunction "GND_51") (pintype "passive"))
      (node (ref "U9") (pin "65") (pinfunction "PAD_65") (pintype "passive"))
      (node (ref "X1") (pin "2") (pinfunction "GND_2") (pintype "passive"))
      (node (ref "X1") (pin "4") (pinfunction "GND_4") (pintype "passive"))
    )
    (net (code "33") (name "Net-(D2-A)") (class "Default")
      (node (ref "D2") (pin "2") (pinfunction "A_2") (pintype "passive"))
      (node (ref "R19") (pin "2") (pinfunction "2_2") (pintype "passive"))
    )
    (net (code "34") (name "Net-(J1-SHLD1)") (class "Default")
      (node (ref "C29") (pin "2") (pinfunction "2_2") (pintype "passive"))
      (node (ref "J1") (pin "10") (pinfunction "SHLD5_10") (pintype "passive"))
      (node (ref "J1") (pin "11") (pinfunction "SHLD6_11") (pintype "passive"))
      (node (ref "J1") (pin "6") (pinfunction "SHLD1_6") (pintype "passive"))
      (node (ref "J1") (pin "7") (pinfunction "SHLD2_7") (pintype "passive"))
      (node (ref "J1") (pin "8") (pinfunction "SHLD3_8") (pintype "passive"))
      (node (ref "J1") (pin "9") (pinfunction "SHLD4_9") (pintype "passive"))
      (node (ref "R9") (pin "1") (pinfunction "1_1") (pintype "passive"))
    )
    (net (code "35") (name "Net-(U9-BDBUS0)") (class "Default")
      (node (ref "RP1") (pin "2") (pinfunction "2_2") (pintype "passive"))
      (node (ref "U9") (pin "26") (pinfunction "BDBUS0_26") (pintype "passive"))
    )
    (net (code "36") (name "Net-(U9-BDBUS1)") (class "Default")
      (node (ref "RP1") (pin "4") (pinfunction "4_4") (pintype "passive"))
      (node (ref "U9") (pin "27") (pinfunction "BDBUS1_27") (pintype "passive"))
    )
    (net (code "37") (name "Net-(U9-BDBUS2)") (class "Default")
      (node (ref "RP1") (pin "6") (pinfunction "6_6") (pintype "passive"))
      (node (ref "U9") (pin "28") (pinfunction "BDBUS2_28") (pintype "passive"))
    )
    (net (code "38") (name "Net-(U9-BDBUS6)") (class "Default")
      (node (ref "R24") (pin "1") (pinfunction "1_1") (pintype "passive"))
      (node (ref "U9") (pin "33") (pinfunction "BDBUS6_33") (pintype "passive"))
    )
    (net (code "39") (name "Net-(U9-DDBUS6)") (class "Default")
      (node (ref "R6") (pin "1") (pinfunction "1_1") (pintype "passive"))
      (node (ref "U9") (pin "58") (pinfunction "DDBUS6_58") (pintype "passive"))
    )
    (net (code "40") (name "Net-(U9-OSCI)") (class "Default")
      (node (ref "C26") (pin "2") (pinfunction "2_2") (pintype "passive"))
      (node (ref "U9") (pin "2") (pinfunction "OSCI_2") (pintype "passive"))
      (node (ref "X1") (pin "3") (pinfunction "B_3") (pintype "passive"))
    )
    (net (code "41") (name "Net-(U9-OSCO)") (class "Default")
      (node (ref "C27") (pin "2") (pinfunction "2_2") (pintype "passive"))
      (node (ref "U9") (pin "3") (pinfunction "OSCO_3") (pintype "passive"))
      (node (ref "X1") (pin "1") (pinfunction "A_1") (pintype "passive"))
    )
    (net (code "42") (name "Net-(U9-REF)") (class "Default")
      (node (ref "R8") (pin "1") (pinfunction "1_1") (pintype "passive"))
      (node (ref "U9") (pin "6") (pinfunction "REF_6") (pintype "passive"))
    )
    (net (code "43") (name "Net-(U9-VPHY)") (class "Default")
      (node (ref "C31") (pin "2") (pinfunction "2_2") (pintype "passive"))
      (node (ref "L2") (pin "1") (pinfunction "1_1") (pintype "passive"))
      (node (ref "U9") (pin "4") (pinfunction "VPHY_4") (pintype "passive"))
    )
    (net (code "44") (name "Net-(U9-VPLL)") (class "Default")
      (node (ref "C28") (pin "2") (pinfunction "2_2") (pintype "passive"))
      (node (ref "L3") (pin "1") (pinfunction "1_1") (pintype "passive"))
      (node (ref "U9") (pin "9") (pinfunction "VPLL_9") (pintype "passive"))
    )
    (net (code "45") (name "Net-(U9-VREGOUT)") (class "Default")
      (node (ref "C30") (pin "2") (pinfunction "2_2") (pintype "passive"))
      (node (ref "U9") (pin "12") (pinfunction "VCORE_12") (pintype "passive"))
      (node (ref "U9") (pin "37") (pinfunction "VCORE_37") (pintype "passive"))
      (node (ref "U9") (pin "49") (pinfunction "VREGOUT_49") (pintype "passive"))
      (node (ref "U9") (pin "64") (pinfunction "VCORE_64") (pintype "passive"))
    )
    (net (code "46") (name "Net-(U11-OUT_Y)") (class "Default")
      (node (ref "U11") (pin "4") (pinfunction "OUT_Y_4") (pintype "passive"))
      (node (ref "U12") (pin "1") (pinfunction "TRIG_1") (pintype "passive"))
    )
    (net (code "47") (name "Net-(U12-DIV)") (class "Default")
      (node (ref "R17") (pin "2") (pinfunction "2_2") (pintype "passive"))
      (node (ref "R18") (pin "1") (pinfunction "1_1") (pintype "passive"))
      (node (ref "U12") (pin "4") (pinfunction "DIV_4") (pintype "passive"))
    )
    (net (code "48") (name "Net-(U12-OUT)") (class "Default")
      (node (ref "R19") (pin "1") (pinfunction "1_1") (pintype "passive"))
      (node (ref "U12") (pin "6") (pinfunction "OUT_6") (pintype "passive"))
    )
    (net (code "49") (name "Net-(U12-SET)") (class "Default")
      (node (ref "R16") (pin "1") (pinfunction "1_1") (pintype "passive"))
      (node (ref "U12") (pin "3") (pinfunction "SET_3") (pintype "passive"))
    )
    (net (code "50") (name "Net-(U13-DO)") (class "Default")
      (node (ref "R10") (pin "1") (pinfunction "1_1") (pintype "passive"))
      (node (ref "R11") (pin "2") (pinfunction "2_2") (pintype "passive"))
      (node (ref "U13") (pin "1") (pinfunction "DO_1") (pintype "passive"))
    )
    (net (code "51") (name "Net-(U14-FB)") (class "Default")
      (node (ref "C23") (pin "1") (pinfunction "1_1") (pintype "passive"))
      (node (ref "R22") (pin "2") (pinfunction "2_2") (pintype "passive"))
      (node (ref "R23") (pin "1") (pinfunction "1_1") (pintype "passive"))
      (node (ref "U14") (pin "5") (pinfunction "FB_5") (pintype "passive"))
    )
    (net (code "52") (name "Net-(U14-SW)") (class "Default")
      (node (ref "L4") (pin "1") (pinfunction "1_1") (pintype "passive"))
      (node (ref "U14") (pin "3") (pinfunction "SW_3") (pintype "passive"))
    )
    (net (code "53") (name "Net-(U15A-1Y)") (class "Default")
      (node (ref "RP2") (pin "5") (pinfunction "5_5") (pintype "passive"))
      (node (ref "U15") (pin "3") (pinfunction "1Y_3") (pintype "passive"))
    )
    (net (code "54") (name "Net-(U15B-2Y)") (class "Default")
      (node (ref "RP2") (pin "3") (pinfunction "3_3") (pintype "passive"))
      (node (ref "U15") (pin "6") (pinfunction "2Y_6") (pintype "passive"))
    )
    (net (code "55") (name "Net-(U15C-3Y)") (class "Default")
      (node (ref "RP2") (pin "1") (pinfunction "1_1") (pintype "passive"))
      (node (ref "U15") (pin "8") (pinfunction "3Y_8") (pintype "passive"))
    )
    (net (code "56") (name "Net-(U15D-4Y)") (class "Default")
      (node (ref "RP2") (pin "7") (pinfunction "7_7") (pintype "passive"))
      (node (ref "U15") (pin "11") (pinfunction "4Y_11") (pintype "passive"))
    )
    (net (code "57") (name "VBUS") (class "Default")
      (node (ref "C22") (pin "2") (pinfunction "2_2") (pintype "passive"))
      (node (ref "J1") (pin "1") (pinfunction "VBUS_1") (pintype "passive"))
      (node (ref "U10") (pin "6") (pinfunction "VDD_6") (pintype "passive"))
      (node (ref "U14") (pin "1") (pinfunction "EN_1") (pintype "passive"))
      (node (ref "U14") (pin "4") (pinfunction "VIN_4") (pintype "passive"))
    )
    (net (code "58") (name "unconnected-(J1-ID-Pad4)") (class "Default")
      (node (ref "J1") (pin "4") (pinfunction "ID_4") (pintype "passive+no_connect"))
    )
    (net (code "59") (name "unconnected-(RP1-Pad7)") (class "Default")
      (node (ref "RP1") (pin "7") (pinfunction "7_7") (pintype "passive+no_connect"))
    )
    (net (code "60") (name "unconnected-(RP1-Pad8)") (class "Default")
      (node (ref "RP1") (pin "8") (pinfunction "8_8") (pintype "passive+no_connect"))
    )
    (net (code "61") (name "unconnected-(U9-ADBUS4-Pad21)") (class "Default")
      (node (ref "U9") (pin "21") (pinfunction "ADBUS4_21") (pintype "passive+no_connect"))
    )
    (net (code "62") (name "unconnected-(U9-ADBUS5-Pad22)") (class "Default")
      (node (ref "U9") (pin "22") (pinfunction "ADBUS5_22") (pintype "passive+no_connect"))
    )
    (net (code "63") (name "unconnected-(U9-ADBUS6-Pad23)") (class "Default")
      (node (ref "U9") (pin "23") (pinfunction "ADBUS6_23") (pintype "passive+no_connect"))
    )
    (net (code "64") (name "unconnected-(U9-ADBUS7-Pad24)") (class "Default")
      (node (ref "U9") (pin "24") (pinfunction "ADBUS7_24") (pintype "passive+no_connect"))
    )
    (net (code "65") (name "unconnected-(U9-BDBUS3-Pad29)") (class "Default")
      (node (ref "U9") (pin "29") (pinfunction "BDBUS3_29") (pintype "passive+no_connect"))
    )
    (net (code "66") (name "unconnected-(U9-BDBUS7-Pad34)") (class "Default")
      (node (ref "U9") (pin "34") (pinfunction "BDBUS7_34") (pintype "passive+no_connect"))
    )
    (net (code "67") (name "unconnected-(U9-CDBUS4-Pad43)") (class "Default")
      (node (ref "U9") (pin "43") (pinfunction "CDBUS4_43") (pintype "passive+no_connect"))
    )
    (net (code "68") (name "unconnected-(U9-CDBUS5-Pad44)") (class "Default")
      (node (ref "U9") (pin "44") (pinfunction "CDBUS5_44") (pintype "passive+no_connect"))
    )
    (net (code "69") (name "unconnected-(U9-CDBUS6-Pad45)") (class "Default")
      (node (ref "U9") (pin "45") (pinfunction "CDBUS6_45") (pintype "passive+no_connect"))
    )
    (net (code "70") (name "unconnected-(U9-CDBUS7-Pad46)") (class "Default")
      (node (ref "U9") (pin "46") (pinfunction "CDBUS7_46") (pintype "passive+no_connect"))
    )
    (net (code "71") (name "unconnected-(U9-DDBUS4-Pad55)") (class "Default")
      (node (ref "U9") (pin "55") (pinfunction "DDBUS4_55") (pintype "passive+no_connect"))
    )
    (net (code "72") (name "unconnected-(U9-DDBUS7-Pad59)") (class "Default")
      (node (ref "U9") (pin "59") (pinfunction "DDBUS7_59") (pintype "passive+no_connect"))
    )
    (net (code "73") (name "unconnected-(U9-~{PWREN}-Pad60)") (class "Default")
      (node (ref "U9") (pin "60") (pinfunction "~{PWREN}_60") (pintype "passive+no_connect"))
    )
    (net (code "74") (name "unconnected-(U9-~{SUSPEND}-Pad36)") (class "Default")
      (node (ref "U9") (pin "36") (pinfunction "~{SUSPEND}_36") (pintype "passive+no_connect"))
    )
  )
)
